# snes-usb-mini_b.net
KiCad netlist of a schematic drawn in EAGLE
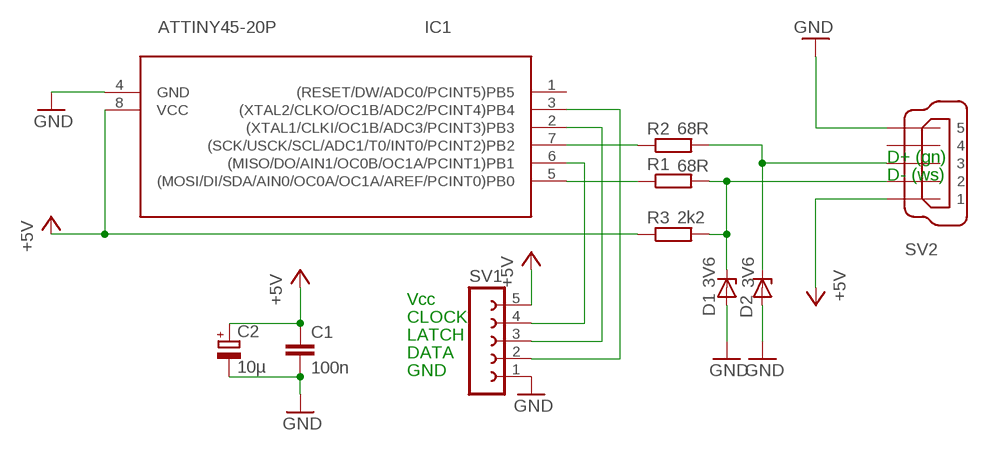
[diagram p0: schematic, sheet 1]

(export (version "E")
  (design (tool "Eeschema 10.0.6"))
  (components
    (comp (ref "C1")
      (value "100n")
      (footprint "eagle-import:C025-024X044")
      (libsource (lib "eagle-import") (part "C-EU025-024X044"))
    )
    (comp (ref "C2")
      (value "10µ")
      (footprint "eagle-import:E2-4")
      (libsource (lib "eagle-import") (part "CPOL-EUE2-4"))
    )
    (comp (ref "D1")
      (value "3V6")
      (footprint "eagle-import:ZDIO-2.5")
      (libsource (lib "eagle-import") (part "ZENER-DIODEZD-2.5"))
    )
    (comp (ref "D2")
      (value "3V6")
      (footprint "eagle-import:ZDIO-2.5")
      (libsource (lib "eagle-import") (part "ZENER-DIODEZD-2.5"))
    )
    (comp (ref "IC1")
      (value "ATTINY45-20P")
      (footprint "eagle-import:DIL08")
      (libsource (lib "eagle-import") (part "ATTINY45P-20"))
    )
    (comp (ref "R1")
      (value "68R")
      (footprint "eagle-import:0207_10")
      (libsource (lib "eagle-import") (part "R-EU_0207/10"))
    )
    (comp (ref "R2")
      (value "68R")
      (footprint "eagle-import:0411V")
      (libsource (lib "eagle-import") (part "R-EU_0411/3V"))
    )
    (comp (ref "R3")
      (value "2k2")
      (footprint "eagle-import:0204V")
      (libsource (lib "eagle-import") (part "R-EU_0204/2V"))
    )
    (comp (ref "SV1")
      (value "FE05-1")
      (footprint "eagle-import:FE05-1")
      (libsource (lib "eagle-import") (part "FE05-1"))
    )
    (comp (ref "SV2")
      (value "MINI-USB_SHIELD5P2-32005-601")
      (footprint "eagle-import:32005-601")
      (libsource (lib "eagle-import") (part "MINI-USB_SHIELD5P2-32005-601"))
    )
  )
  (nets
    (net (code "1") (name "+5V") (class "Default")
      (node (ref "C1") (pin "1") (pinfunction "1_1") (pintype "passive"))
      (node (ref "C2") (pin "+") (pinfunction "+_+") (pintype "passive"))
      (node (ref "IC1") (pin "8") (pinfunction "VCC_8") (pintype "bidirectional"))
      (node (ref "R3") (pin "1") (pinfunction "1_1") (pintype "passive"))
      (node (ref "SV1") (pin "5") (pinfunction "5_5") (pintype "passive"))
      (node (ref "SV2") (pin "1") (pinfunction "1_1") (pintype "passive"))
    )
    (net (code "2") (name "GND") (class "Default")
      (node (ref "C1") (pin "2") (pinfunction "2_2") (pintype "passive"))
      (node (ref "C2") (pin "-") (pinfunction "-_-") (pintype "passive"))
      (node (ref "D1") (pin "A") (pinfunction "A_A") (pintype "passive"))
      (node (ref "D2") (pin "A") (pinfunction "A_A") (pintype "passive"))
      (node (ref "IC1") (pin "4") (pinfunction "GND_4") (pintype "bidirectional"))
      (node (ref "SV1") (pin "1") (pinfunction "1_1") (pintype "passive"))
      (node (ref "SV2") (pin "5") (pinfunction "5_5") (pintype "passive"))
    )
    (net (code "3") (name "Net-(D1-PadC)") (class "Default")
      (node (ref "D1") (pin "C") (pinfunction "C_C") (pintype "passive"))
      (node (ref "R1") (pin "2") (pinfunction "2_2") (pintype "passive"))
      (node (ref "R3") (pin "2") (pinfunction "2_2") (pintype "passive"))
      (node (ref "SV2") (pin "2") (pinfunction "2_2") (pintype "passive"))
    )
    (net (code "4") (name "Net-(D2-PadC)") (class "Default")
      (node (ref "D2") (pin "C") (pinfunction "C_C") (pintype "passive"))
      (node (ref "R2") (pin "2") (pinfunction "2_2") (pintype "passive"))
      (node (ref "SV2") (pin "3") (pinfunction "3_3") (pintype "passive"))
    )
    (net (code "5") (name "Net-(IC1-(MISO{slash}DO{slash}AIN1{slash}OC0B{slash}OC1A{slash}PCINT1)PB1)") (class "Default")
      (node (ref "IC1") (pin "6") (pinfunction "(MISO/DO/AIN1/OC0B/OC1A/PCINT1)PB1_6") (pintype "bidirectional"))
      (node (ref "SV1") (pin "4") (pinfunction "4_4") (pintype "passive"))
    )
    (net (code "6") (name "Net-(IC1-(MOSI{slash}DI{slash}SDA{slash}AIN0{slash}OC0A{slash}OC1A{slash}AREF{slash}PCINT0)PB0)") (class "Default")
      (node (ref "IC1") (pin "5") (pinfunction "(MOSI/DI/SDA/AIN0/OC0A/OC1A/AREF/PCINT0)PB0_5") (pintype "bidirectional"))
      (node (ref "R1") (pin "1") (pinfunction "1_1") (pintype "passive"))
    )
    (net (code "7") (name "Net-(IC1-(SCK{slash}USCK{slash}SCL{slash}ADC1{slash}T0{slash}INT0{slash}PCINT2)PB2)") (class "Default")
      (node (ref "IC1") (pin "7") (pinfunction "(SCK/USCK/SCL/ADC1/T0/INT0/PCINT2)PB2_7") (pintype "bidirectional"))
      (node (ref "R2") (pin "1") (pinfunction "1_1") (pintype "passive"))
    )
    (net (code "8") (name "Net-(IC1-(XTAL1{slash}CLKI{slash}OC1B{slash}ADC3{slash}PCINT3)PB3)") (class "Default")
      (node (ref "IC1") (pin "2") (pinfunction "(XTAL1/CLKI/OC1B/ADC3/PCINT3)PB3_2") (pintype "bidirectional"))
      (node (ref "SV1") (pin "3") (pinfunction "3_3") (pintype "passive"))
    )
    (net (code "9") (name "Net-(IC1-(XTAL2{slash}CLKO{slash}OC1B{slash}ADC2{slash}PCINT4)PB4)") (class "Default")
      (node (ref "IC1") (pin "3") (pinfunction "(XTAL2/CLKO/OC1B/ADC2/PCINT4)PB4_3") (pintype "bidirectional"))
      (node (ref "SV1") (pin "2") (pinfunction "2_2") (pintype "passive"))
    )
    (net (code "10") (name "unconnected-(IC1-(RESET{slash}DW{slash}ADC0{slash}PCINT5)PB5-Pad1)") (class "Default")
      (node (ref "IC1") (pin "1") (pinfunction "(RESET/DW/ADC0/PCINT5)PB5_1") (pintype "bidirectional"))
    )
    (net (code "11") (name "unconnected-(SV2-Pad4)") (class "Default")
      (node (ref "SV2") (pin "4") (pinfunction "4_4") (pintype "passive"))
    )
  )
)
